# LEDActuatorJack.net
KiCad netlist of a schematic drawn in EAGLE
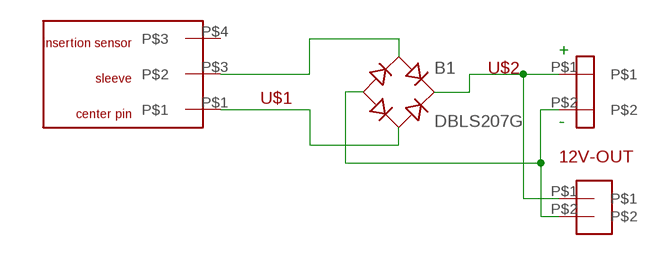
[diagram p0: schematic, sheet 1]

(export (version "E")
  (design (tool "Eeschema 10.0.6"))
  (components
    (comp (ref "12V-OUT")
      (value "1X2HEADER_ROBBIE")
      (footprint "eagle-import:1X2HEADER_ROBBIE")
      (libsource (lib "eagle-import") (part "1X2HEADER_ROBBIE"))
    )
    (comp (ref "B1")
      (value "DBLS207G")
      (footprint "eagle-import:DBS")
      (libsource (lib "eagle-import") (part "DB?GLS207"))
    )
    (comp (ref "U$1")
      (value "PJ-014CH-SMT")
      (footprint "eagle-import:PJ-014CH-SMT")
      (libsource (lib "eagle-import") (part "PJ-014CH-SMT"))
    )
    (comp (ref "U$2")
      (value "3.5MM_2PIN_SCREWTERMINAL_SPARKFUN")
      (footprint "eagle-import:1X02_3.5_SCREWTERM")
      (libsource (lib "eagle-import") (part "3.5MM_2PIN_SCREWTERMINAL_SPARKFUN"))
    )
  )
  (nets
    (net (code "1") (name "Net-(12V-OUT-PadP$1)") (class "Default")
      (node (ref "12V-OUT") (pin "P$1") (pinfunction "P$1_P$1") (pintype "bidirectional"))
      (node (ref "B1") (pin "+") (pinfunction "+_+") (pintype "passive"))
      (node (ref "U$2") (pin "P$1") (pinfunction "P$1_P$1") (pintype "bidirectional"))
    )
    (net (code "2") (name "Net-(12V-OUT-PadP$2)") (class "Default")
      (node (ref "12V-OUT") (pin "P$2") (pinfunction "P$2_P$2") (pintype "bidirectional"))
      (node (ref "B1") (pin "-") (pinfunction "-_-") (pintype "passive"))
      (node (ref "U$2") (pin "P$2") (pinfunction "P$2_P$2") (pintype "bidirectional"))
    )
    (net (code "3") (name "Net-(B1-PadAC2)") (class "Default")
      (node (ref "B1") (pin "AC2") (pinfunction "AC2_AC2") (pintype "passive"))
      (node (ref "U$1") (pin "P$1") (pinfunction "P$1_P$1") (pintype "bidirectional"))
    )
    (net (code "4") (name "Net-(U$1-P$2)") (class "Default")
      (node (ref "B1") (pin "AC1") (pinfunction "AC1_AC1") (pintype "passive"))
      (node (ref "U$1") (pin "P$3") (pinfunction "P$2_P$3") (pintype "bidirectional"))
    )
    (net (code "5") (name "unconnected-(U$1-P$3-PadP$4)") (class "Default")
      (node (ref "U$1") (pin "P$4") (pinfunction "P$3_P$4") (pintype "bidirectional"))
    )
  )
)
